# ProProject_Adapter_1_0.net
KiCad netlist of a schematic drawn in EasyEDA Pro
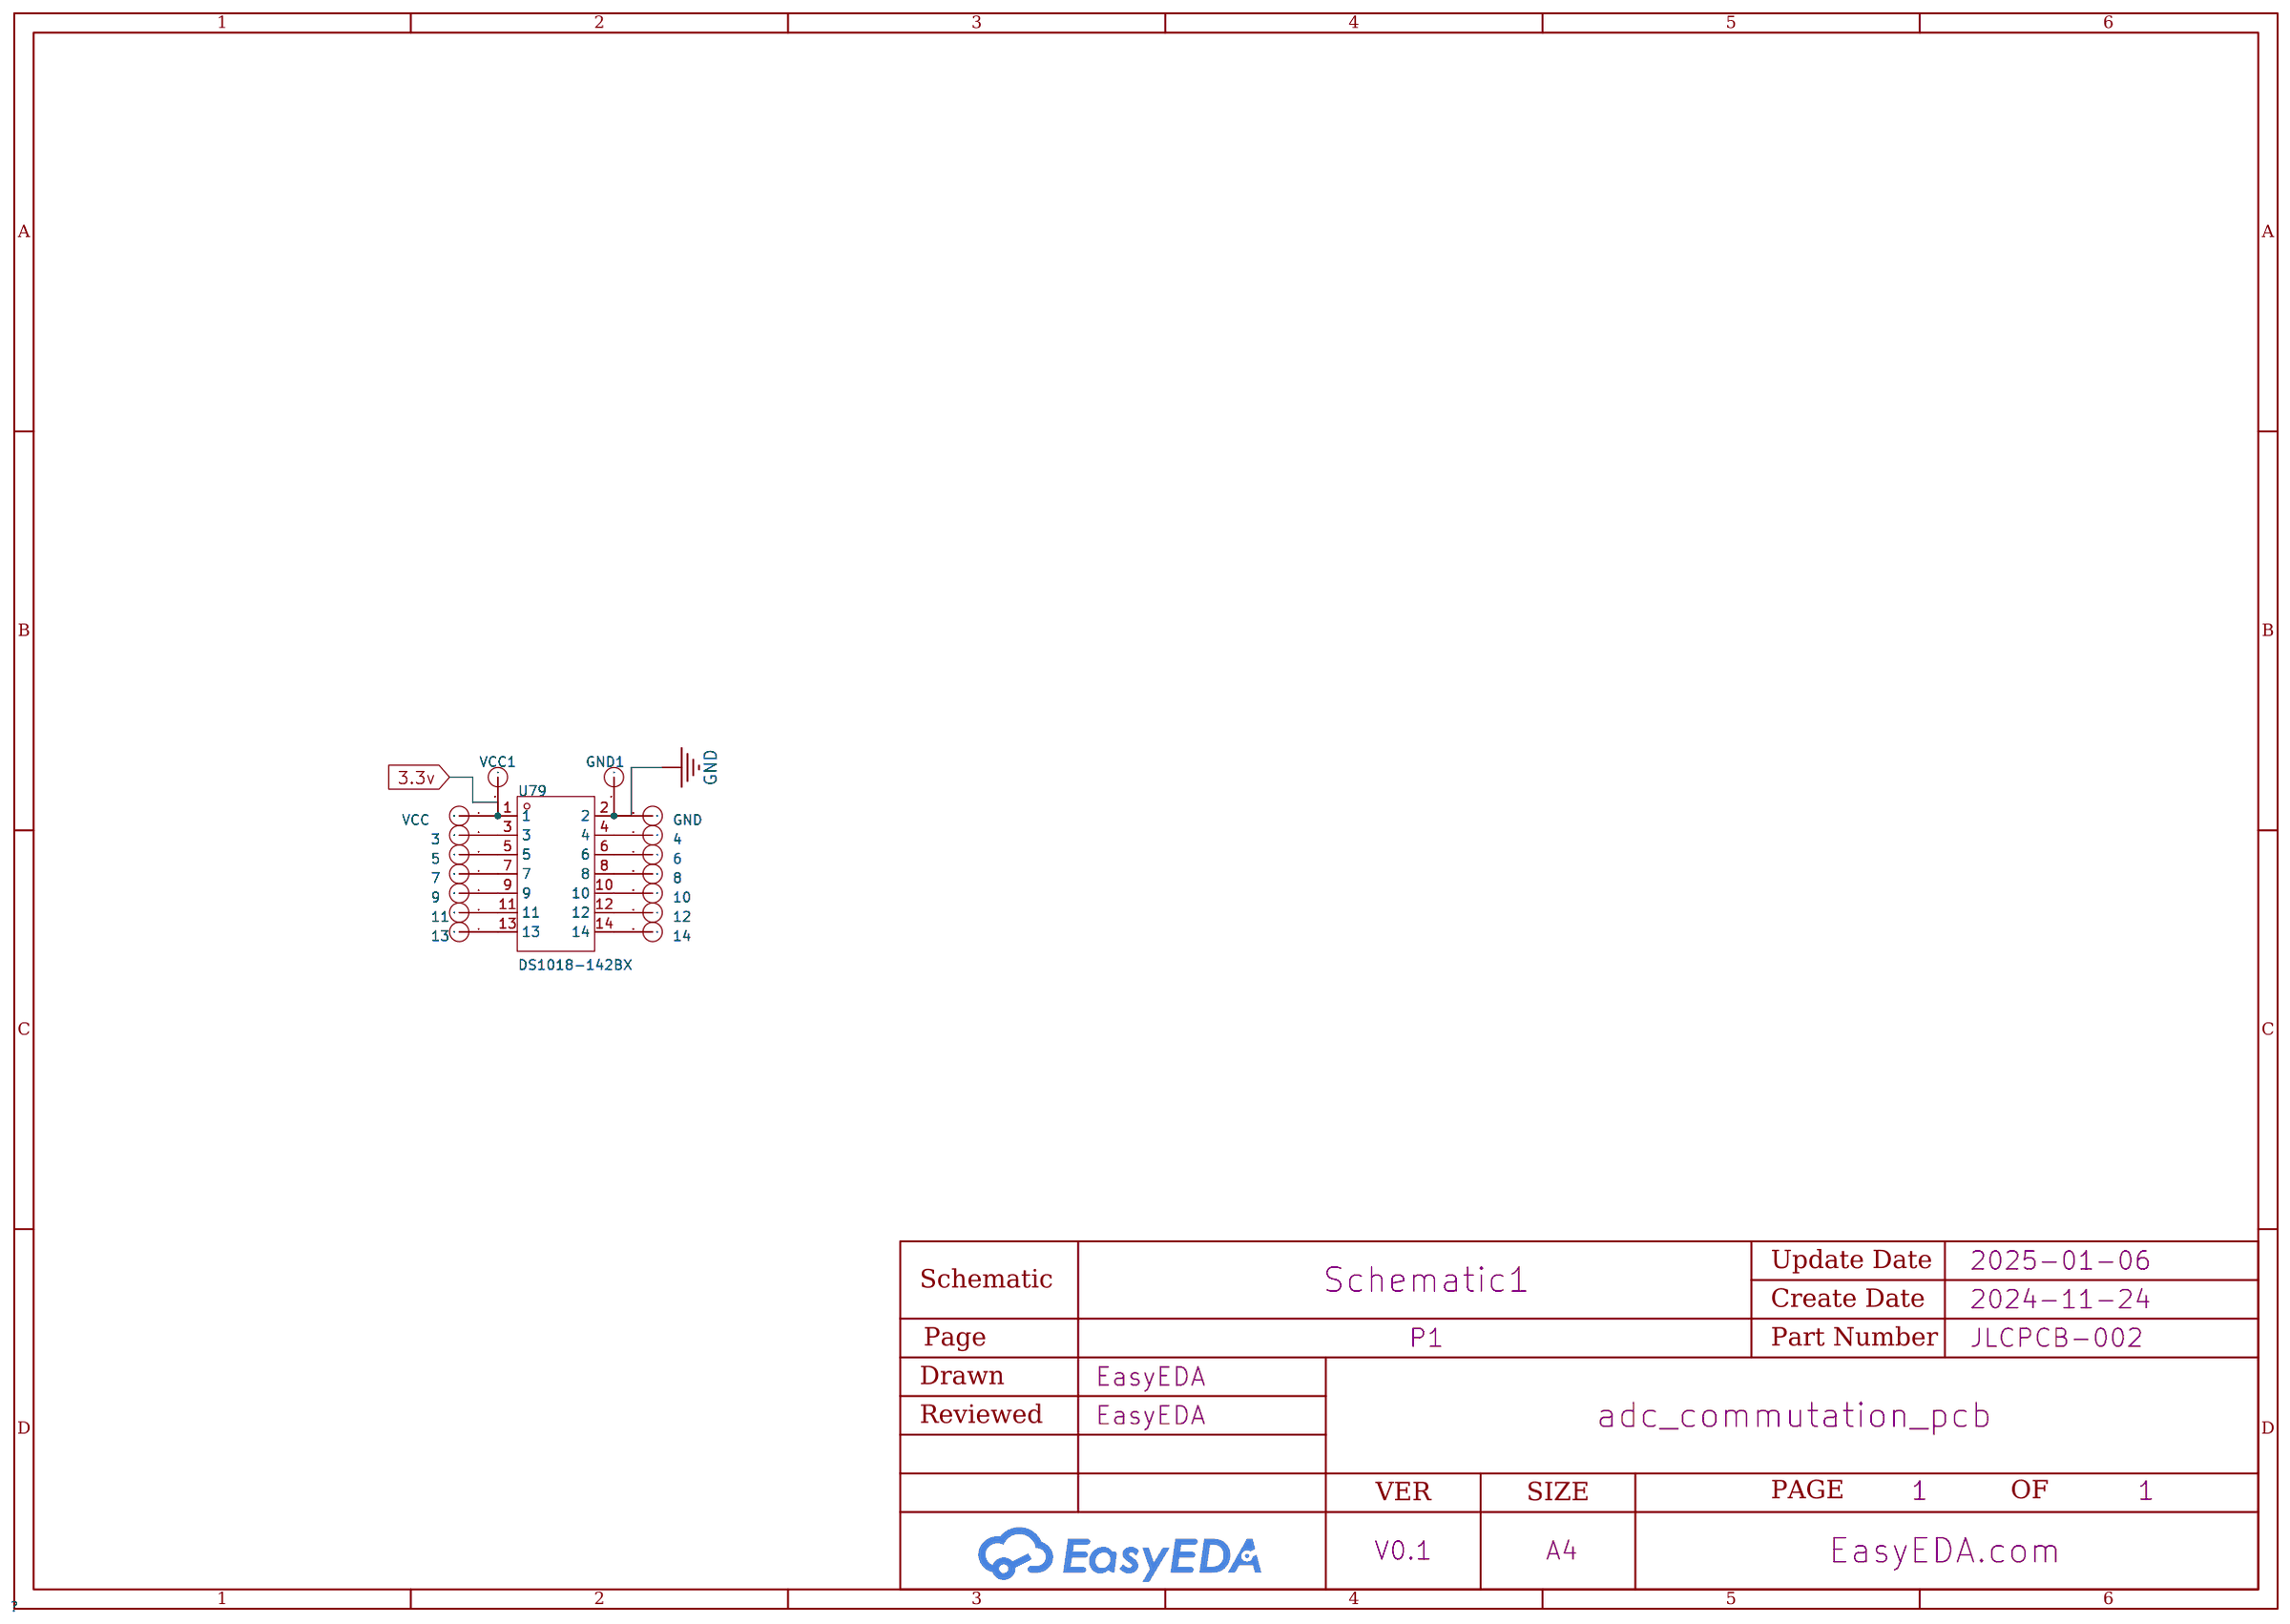
[diagram p0: schematic sheet]

(export (version "E")
  (design (tool "Eeschema 10.0.6"))
  (components
    (comp (ref "3")
      (value "~")
      (footprint "easyedapro:robust_pin")
      (libsource (lib "easyedapro") (part "robust_pin"))
    )
    (comp (ref "4")
      (value "~")
      (footprint "easyedapro:robust_pin")
      (libsource (lib "easyedapro") (part "robust_pin"))
    )
    (comp (ref "5")
      (value "~")
      (footprint "easyedapro:robust_pin")
      (libsource (lib "easyedapro") (part "robust_pin"))
    )
    (comp (ref "6")
      (value "~")
      (footprint "easyedapro:robust_pin")
      (libsource (lib "easyedapro") (part "robust_pin"))
    )
    (comp (ref "7")
      (value "~")
      (footprint "easyedapro:robust_pin")
      (libsource (lib "easyedapro") (part "robust_pin"))
    )
    (comp (ref "8")
      (value "~")
      (footprint "easyedapro:robust_pin")
      (libsource (lib "easyedapro") (part "robust_pin"))
    )
    (comp (ref "9")
      (value "~")
      (footprint "easyedapro:robust_pin")
      (libsource (lib "easyedapro") (part "robust_pin"))
    )
    (comp (ref "10")
      (value "~")
      (footprint "easyedapro:robust_pin")
      (libsource (lib "easyedapro") (part "robust_pin"))
    )
    (comp (ref "11")
      (value "~")
      (footprint "easyedapro:robust_pin")
      (libsource (lib "easyedapro") (part "robust_pin"))
    )
    (comp (ref "12")
      (value "~")
      (footprint "easyedapro:robust_pin")
      (libsource (lib "easyedapro") (part "robust_pin"))
    )
    (comp (ref "13")
      (value "~")
      (footprint "easyedapro:robust_pin")
      (libsource (lib "easyedapro") (part "robust_pin"))
    )
    (comp (ref "14")
      (value "~")
      (footprint "easyedapro:robust_pin")
      (libsource (lib "easyedapro") (part "robust_pin"))
    )
    (comp (ref "GND")
      (value "~")
      (footprint "easyedapro:robust_pin")
      (libsource (lib "easyedapro") (part "robust_pin"))
    )
    (comp (ref "GND1")
      (value "~")
      (footprint "easyedapro:robust_pin")
      (libsource (lib "easyedapro") (part "robust_pin"))
    )
    (comp (ref "U79")
      (value "DS1018-142BX")
      (footprint "easyedapro:HDR-TH_14P-P2.54_CONNFLY_DS1018-142BX")
      (description "Pitch:2.54mm Structure:2x7P Number of Rows:2 Pin Number in each Row:7")
      (fields (field (name "Manufacturer") "CONNFLY"))
      (libsource (lib "easyedapro") (part "DS1018-142BX"))
    )
    (comp (ref "VCC")
      (value "~")
      (footprint "easyedapro:robust_pin")
      (libsource (lib "easyedapro") (part "robust_pin"))
    )
    (comp (ref "VCC1")
      (value "~")
      (footprint "easyedapro:robust_pin")
      (libsource (lib "easyedapro") (part "robust_pin"))
    )
  )
  (nets
    (net (code "1") (name "3.3v") (class "Default")
      (node (ref "U79") (pin "1") (pinfunction "1_1") (pintype "unspecified"))
      (node (ref "VCC") (pin "1") (pinfunction "1_1") (pintype "input"))
      (node (ref "VCC1") (pin "1") (pinfunction "1_1") (pintype "input"))
    )
    (net (code "2") (name "GND") (class "Default")
      (node (ref "GND") (pin "1") (pinfunction "1_1") (pintype "input"))
      (node (ref "GND1") (pin "1") (pinfunction "1_1") (pintype "input"))
      (node (ref "U79") (pin "2") (pinfunction "2_2") (pintype "unspecified"))
    )
    (net (code "3") (name "Net-(3-Pad1)") (class "Default")
      (node (ref "3") (pin "1") (pinfunction "1_1") (pintype "input"))
      (node (ref "U79") (pin "3") (pinfunction "3_3") (pintype "unspecified"))
    )
    (net (code "4") (name "Net-(4-Pad1)") (class "Default")
      (node (ref "4") (pin "1") (pinfunction "1_1") (pintype "input"))
      (node (ref "U79") (pin "4") (pinfunction "4_4") (pintype "unspecified"))
    )
    (net (code "5") (name "Net-(5-Pad1)") (class "Default")
      (node (ref "5") (pin "1") (pinfunction "1_1") (pintype "input"))
      (node (ref "U79") (pin "5") (pinfunction "5_5") (pintype "unspecified"))
    )
    (net (code "6") (name "Net-(6-Pad1)") (class "Default")
      (node (ref "6") (pin "1") (pinfunction "1_1") (pintype "input"))
      (node (ref "U79") (pin "6") (pinfunction "6_6") (pintype "unspecified"))
    )
    (net (code "7") (name "Net-(7-Pad1)") (class "Default")
      (node (ref "7") (pin "1") (pinfunction "1_1") (pintype "input"))
      (node (ref "U79") (pin "7") (pinfunction "7_7") (pintype "unspecified"))
    )
    (net (code "8") (name "Net-(8-Pad1)") (class "Default")
      (node (ref "8") (pin "1") (pinfunction "1_1") (pintype "input"))
      (node (ref "U79") (pin "8") (pinfunction "8_8") (pintype "unspecified"))
    )
    (net (code "9") (name "Net-(9-Pad1)") (class "Default")
      (node (ref "9") (pin "1") (pinfunction "1_1") (pintype "input"))
      (node (ref "U79") (pin "9") (pinfunction "9_9") (pintype "unspecified"))
    )
    (net (code "10") (name "Net-(10-Pad1)") (class "Default")
      (node (ref "10") (pin "1") (pinfunction "1_1") (pintype "input"))
      (node (ref "U79") (pin "10") (pinfunction "10_10") (pintype "unspecified"))
    )
    (net (code "11") (name "Net-(11-Pad1)") (class "Default")
      (node (ref "11") (pin "1") (pinfunction "1_1") (pintype "input"))
      (node (ref "U79") (pin "11") (pinfunction "11_11") (pintype "unspecified"))
    )
    (net (code "12") (name "Net-(12-Pad1)") (class "Default")
      (node (ref "12") (pin "1") (pinfunction "1_1") (pintype "input"))
      (node (ref "U79") (pin "12") (pinfunction "12_12") (pintype "unspecified"))
    )
    (net (code "13") (name "Net-(13-Pad1)") (class "Default")
      (node (ref "13") (pin "1") (pinfunction "1_1") (pintype "input"))
      (node (ref "U79") (pin "13") (pinfunction "13_13") (pintype "unspecified"))
    )
    (net (code "14") (name "Net-(14-Pad1)") (class "Default")
      (node (ref "14") (pin "1") (pinfunction "1_1") (pintype "input"))
      (node (ref "U79") (pin "14") (pinfunction "14_14") (pintype "unspecified"))
    )
  )
)
